# Jafar_-_EasyEDA_-_Schematic_Export.net
KiCad netlist of a schematic drawn in EasyEDA
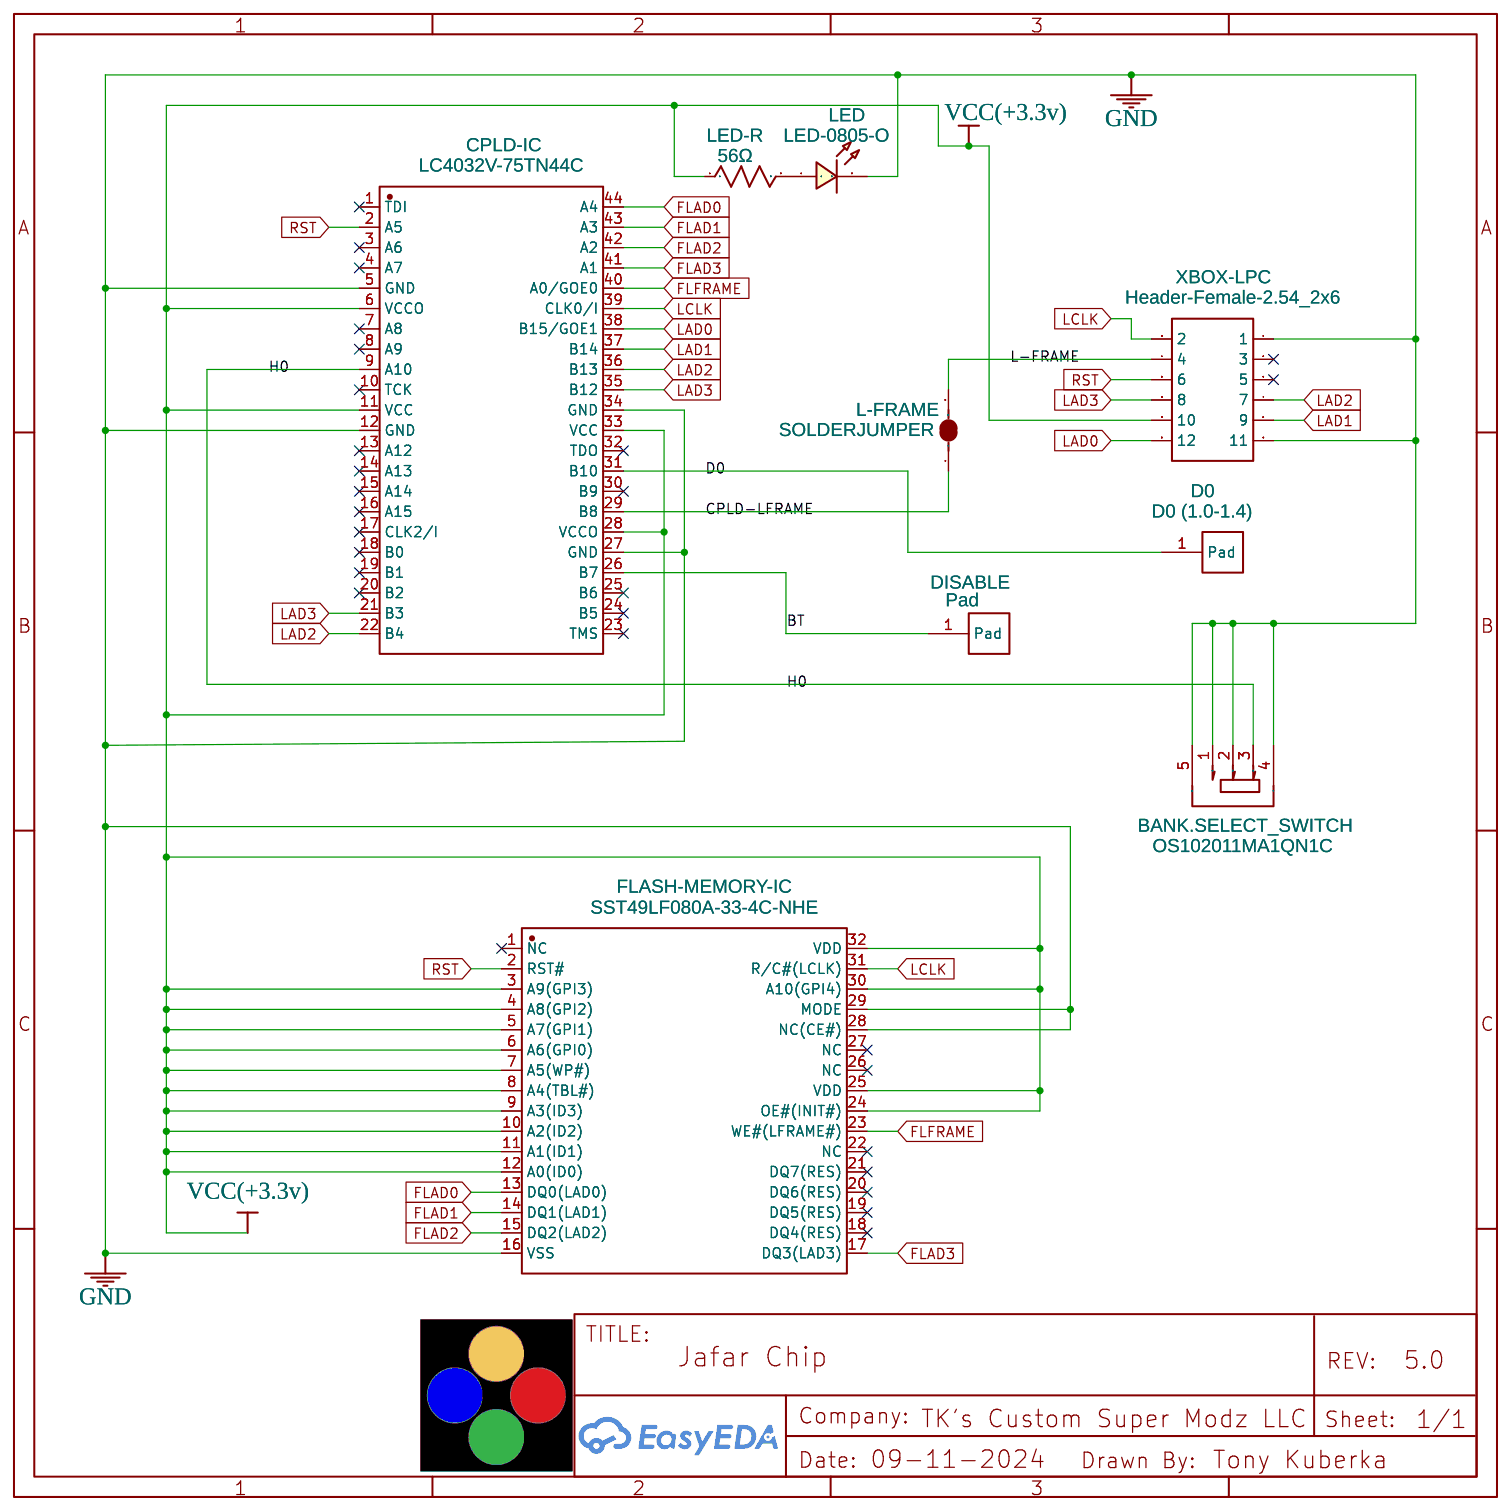
[diagram p0: schematic sheet]

(export (version "E")
  (design (tool "Eeschema 10.0.6"))
  (components
    (comp (ref "BANK.SELECT_SWITCH")
      (value "OS102011MA1QN1C")
      (fields (field (name "Manufacturer") "C&K"))
      (libsource (lib "") (part "OS102011MA1QN1C"))
    )
    (comp (ref "CPLD-IC")
      (value "LC4032V-75TN44C")
      (fields (field (name "Manufacturer") "LATTICE(莱迪思)"))
      (libsource (lib "") (part "LC4032V-75TN44C"))
    )
    (comp (ref "D0") (value "D0 (1.0-1.4)") (libsource (lib "") (part "SOLDER PAD_1")))
    (comp (ref "DISABLE") (value "Pad") (libsource (lib "") (part "SOLDER PAD")))
    (comp (ref "FLASH-MEMORY-IC")
      (value "SST49LF080A-33-4C-NHE")
      (fields (field (name "Manufacturer") "MICROCHIP(美国微芯)"))
      (libsource (lib "") (part "SST49LF080A-33-4C-NHE"))
    )
    (comp (ref "L-FRAME") (value "SOLDERJUMPER") (libsource (lib "") (part "SOLDERJUMPER-OLDNC2")))
    (comp (ref "LED")
      (value "LED-0805-O")
      (fields
        (field (name "Manufacturer Part") "SZYY0805O")
        (field (name "Manufacturer") "Yongyu Photoelectric")
      )
      (libsource (lib "") (part "LED-0805-ORANGE"))
    )
    (comp (ref "LED-R") (value "56Ω") (libsource (lib "") (part "R_0805_US")))
    (comp (ref "XBOX-LPC")
      (value "Header-Female-2.54_2x6")
      (fields (field (name "Manufacturer Part") "2.54-2*6P母") (field (name "Manufacturer") "BOOMELE(博穆精密)"))
      (libsource (lib "") (part "Header-Female-2.54_2x6"))
    )
  )
  (nets
    (net (code "1") (name "/BT") (class "Default")
      (node (ref "CPLD-IC") (pin "26") (pinfunction "B7_26") (pintype "unspecified"))
      (node (ref "DISABLE") (pin "1") (pinfunction "Pad_1") (pintype "unspecified"))
    )
    (net (code "2") (name "/CPLD-LFRAME") (class "Default")
      (node (ref "CPLD-IC") (pin "29") (pinfunction "B8_29") (pintype "unspecified"))
      (node (ref "L-FRAME") (pin "1") (pinfunction "1_1") (pintype "unspecified"))
    )
    (net (code "3") (name "/D0") (class "Default")
      (node (ref "CPLD-IC") (pin "31") (pinfunction "B10_31") (pintype "unspecified"))
      (node (ref "D0") (pin "1") (pinfunction "Pad_1") (pintype "unspecified"))
    )
    (net (code "4") (name "/H0") (class "Default")
      (node (ref "BANK.SELECT_SWITCH") (pin "3") (pinfunction "3_3") (pintype "unspecified"))
      (node (ref "CPLD-IC") (pin "9") (pinfunction "A10_9") (pintype "unspecified"))
    )
    (net (code "5") (name "/L-FRAME") (class "Default")
      (node (ref "L-FRAME") (pin "2") (pinfunction "2_2") (pintype "unspecified"))
      (node (ref "XBOX-LPC") (pin "4") (pinfunction "4_4") (pintype "input"))
    )
    (net (code "6") (name "FLAD0") (class "Default")
      (node (ref "CPLD-IC") (pin "44") (pinfunction "A4_44") (pintype "unspecified"))
      (node (ref "FLASH-MEMORY-IC") (pin "13") (pinfunction "DQ0(LAD0)_13") (pintype "unspecified"))
    )
    (net (code "7") (name "FLAD1") (class "Default")
      (node (ref "CPLD-IC") (pin "43") (pinfunction "A3_43") (pintype "unspecified"))
      (node (ref "FLASH-MEMORY-IC") (pin "14") (pinfunction "DQ1(LAD1)_14") (pintype "unspecified"))
    )
    (net (code "8") (name "FLAD2") (class "Default")
      (node (ref "CPLD-IC") (pin "42") (pinfunction "A2_42") (pintype "unspecified"))
      (node (ref "FLASH-MEMORY-IC") (pin "15") (pinfunction "DQ2(LAD2)_15") (pintype "unspecified"))
    )
    (net (code "9") (name "FLAD3") (class "Default")
      (node (ref "CPLD-IC") (pin "41") (pinfunction "A1_41") (pintype "unspecified"))
      (node (ref "FLASH-MEMORY-IC") (pin "17") (pinfunction "DQ3(LAD3)_17") (pintype "unspecified"))
    )
    (net (code "10") (name "FLFRAME") (class "Default")
      (node (ref "CPLD-IC") (pin "40") (pinfunction "A0/GOE0_40") (pintype "unspecified"))
      (node (ref "FLASH-MEMORY-IC") (pin "23") (pinfunction "WE#(LFRAME#)_23") (pintype "unspecified"))
    )
    (net (code "11") (name "GND") (class "Default")
      (node (ref "BANK.SELECT_SWITCH") (pin "1") (pinfunction "1_1") (pintype "unspecified"))
      (node (ref "BANK.SELECT_SWITCH") (pin "2") (pinfunction "2_2") (pintype "unspecified"))
      (node (ref "BANK.SELECT_SWITCH") (pin "4") (pinfunction "4_4") (pintype "unspecified"))
      (node (ref "BANK.SELECT_SWITCH") (pin "5") (pinfunction "5_5") (pintype "unspecified"))
      (node (ref "CPLD-IC") (pin "12") (pinfunction "GND_12") (pintype "unspecified"))
      (node (ref "CPLD-IC") (pin "27") (pinfunction "GND_27") (pintype "unspecified"))
      (node (ref "CPLD-IC") (pin "34") (pinfunction "GND_34") (pintype "unspecified"))
      (node (ref "CPLD-IC") (pin "5") (pinfunction "GND_5") (pintype "unspecified"))
      (node (ref "FLASH-MEMORY-IC") (pin "16") (pinfunction "VSS_16") (pintype "unspecified"))
      (node (ref "FLASH-MEMORY-IC") (pin "28") (pinfunction "NC(CE#)_28") (pintype "unspecified"))
      (node (ref "FLASH-MEMORY-IC") (pin "29") (pinfunction "MODE_29") (pintype "unspecified"))
      (node (ref "LED") (pin "2") (pinfunction "2_2") (pintype "unspecified"))
      (node (ref "XBOX-LPC") (pin "1") (pinfunction "1_1") (pintype "input"))
      (node (ref "XBOX-LPC") (pin "11") (pinfunction "11_11") (pintype "input"))
    )
    (net (code "12") (name "LAD0") (class "Default")
      (node (ref "CPLD-IC") (pin "38") (pinfunction "B15/GOE1_38") (pintype "unspecified"))
      (node (ref "XBOX-LPC") (pin "12") (pinfunction "12_12") (pintype "input"))
    )
    (net (code "13") (name "LAD1") (class "Default")
      (node (ref "CPLD-IC") (pin "37") (pinfunction "B14_37") (pintype "unspecified"))
      (node (ref "XBOX-LPC") (pin "9") (pinfunction "9_9") (pintype "input"))
    )
    (net (code "14") (name "LAD2") (class "Default")
      (node (ref "CPLD-IC") (pin "22") (pinfunction "B4_22") (pintype "unspecified"))
      (node (ref "CPLD-IC") (pin "36") (pinfunction "B13_36") (pintype "unspecified"))
      (node (ref "XBOX-LPC") (pin "7") (pinfunction "7_7") (pintype "input"))
    )
    (net (code "15") (name "LAD3") (class "Default")
      (node (ref "CPLD-IC") (pin "21") (pinfunction "B3_21") (pintype "unspecified"))
      (node (ref "CPLD-IC") (pin "35") (pinfunction "B12_35") (pintype "unspecified"))
      (node (ref "XBOX-LPC") (pin "8") (pinfunction "8_8") (pintype "input"))
    )
    (net (code "16") (name "LCLK") (class "Default")
      (node (ref "CPLD-IC") (pin "39") (pinfunction "CLK0/I_39") (pintype "unspecified"))
      (node (ref "FLASH-MEMORY-IC") (pin "31") (pinfunction "R/C#(LCLK)_31") (pintype "unspecified"))
      (node (ref "XBOX-LPC") (pin "2") (pinfunction "2_2") (pintype "input"))
    )
    (net (code "17") (name "Net-(LED-Pad1)") (class "Default")
      (node (ref "LED") (pin "1") (pinfunction "1_1") (pintype "unspecified"))
      (node (ref "LED-R") (pin "2") (pinfunction "2_2") (pintype "unspecified"))
    )
    (net (code "18") (name "RST") (class "Default")
      (node (ref "CPLD-IC") (pin "2") (pinfunction "A5_2") (pintype "unspecified"))
      (node (ref "FLASH-MEMORY-IC") (pin "2") (pinfunction "RST#_2") (pintype "unspecified"))
      (node (ref "XBOX-LPC") (pin "6") (pinfunction "6_6") (pintype "input"))
    )
    (net (code "19") (name "VCC(+3.3v)") (class "Default")
      (node (ref "CPLD-IC") (pin "11") (pinfunction "VCC_11") (pintype "unspecified"))
      (node (ref "CPLD-IC") (pin "28") (pinfunction "VCCO_28") (pintype "unspecified"))
      (node (ref "CPLD-IC") (pin "33") (pinfunction "VCC_33") (pintype "unspecified"))
      (node (ref "CPLD-IC") (pin "6") (pinfunction "VCCO_6") (pintype "unspecified"))
      (node (ref "FLASH-MEMORY-IC") (pin "10") (pinfunction "A2(ID2)_10") (pintype "unspecified"))
      (node (ref "FLASH-MEMORY-IC") (pin "11") (pinfunction "A1(ID1)_11") (pintype "unspecified"))
      (node (ref "FLASH-MEMORY-IC") (pin "12") (pinfunction "A0(ID0)_12") (pintype "unspecified"))
      (node (ref "FLASH-MEMORY-IC") (pin "24") (pinfunction "OE#(INIT#)_24") (pintype "unspecified"))
      (node (ref "FLASH-MEMORY-IC") (pin "25") (pinfunction "VDD_25") (pintype "unspecified"))
      (node (ref "FLASH-MEMORY-IC") (pin "3") (pinfunction "A9(GPI3)_3") (pintype "unspecified"))
      (node (ref "FLASH-MEMORY-IC") (pin "30") (pinfunction "A10(GPI4)_30") (pintype "unspecified"))
      (node (ref "FLASH-MEMORY-IC") (pin "32") (pinfunction "VDD_32") (pintype "unspecified"))
      (node (ref "FLASH-MEMORY-IC") (pin "4") (pinfunction "A8(GPI2)_4") (pintype "unspecified"))
      (node (ref "FLASH-MEMORY-IC") (pin "5") (pinfunction "A7(GPI1)_5") (pintype "unspecified"))
      (node (ref "FLASH-MEMORY-IC") (pin "6") (pinfunction "A6(GPI0)_6") (pintype "unspecified"))
      (node (ref "FLASH-MEMORY-IC") (pin "7") (pinfunction "A5(WP#)_7") (pintype "unspecified"))
      (node (ref "FLASH-MEMORY-IC") (pin "8") (pinfunction "A4(TBL#)_8") (pintype "unspecified"))
      (node (ref "FLASH-MEMORY-IC") (pin "9") (pinfunction "A3(ID3)_9") (pintype "unspecified"))
      (node (ref "LED-R") (pin "1") (pinfunction "1_1") (pintype "unspecified"))
      (node (ref "XBOX-LPC") (pin "10") (pinfunction "10_10") (pintype "input"))
    )
    (net (code "20") (name "unconnected-(CPLD-IC-A6-Pad3)") (class "Default")
      (node (ref "CPLD-IC") (pin "3") (pinfunction "A6_3") (pintype "unspecified+no_connect"))
    )
    (net (code "21") (name "unconnected-(CPLD-IC-A7-Pad4)") (class "Default")
      (node (ref "CPLD-IC") (pin "4") (pinfunction "A7_4") (pintype "unspecified+no_connect"))
    )
    (net (code "22") (name "unconnected-(CPLD-IC-A8-Pad7)") (class "Default")
      (node (ref "CPLD-IC") (pin "7") (pinfunction "A8_7") (pintype "unspecified+no_connect"))
    )
    (net (code "23") (name "unconnected-(CPLD-IC-A9-Pad8)") (class "Default")
      (node (ref "CPLD-IC") (pin "8") (pinfunction "A9_8") (pintype "unspecified+no_connect"))
    )
    (net (code "24") (name "unconnected-(CPLD-IC-A12-Pad13)") (class "Default")
      (node (ref "CPLD-IC") (pin "13") (pinfunction "A12_13") (pintype "unspecified+no_connect"))
    )
    (net (code "25") (name "unconnected-(CPLD-IC-A13-Pad14)") (class "Default")
      (node (ref "CPLD-IC") (pin "14") (pinfunction "A13_14") (pintype "unspecified+no_connect"))
    )
    (net (code "26") (name "unconnected-(CPLD-IC-A14-Pad15)") (class "Default")
      (node (ref "CPLD-IC") (pin "15") (pinfunction "A14_15") (pintype "unspecified+no_connect"))
    )
    (net (code "27") (name "unconnected-(CPLD-IC-A15-Pad16)") (class "Default")
      (node (ref "CPLD-IC") (pin "16") (pinfunction "A15_16") (pintype "unspecified+no_connect"))
    )
    (net (code "28") (name "unconnected-(CPLD-IC-B0-Pad18)") (class "Default")
      (node (ref "CPLD-IC") (pin "18") (pinfunction "B0_18") (pintype "unspecified+no_connect"))
    )
    (net (code "29") (name "unconnected-(CPLD-IC-B1-Pad19)") (class "Default")
      (node (ref "CPLD-IC") (pin "19") (pinfunction "B1_19") (pintype "unspecified+no_connect"))
    )
    (net (code "30") (name "unconnected-(CPLD-IC-B2-Pad20)") (class "Default")
      (node (ref "CPLD-IC") (pin "20") (pinfunction "B2_20") (pintype "unspecified+no_connect"))
    )
    (net (code "31") (name "unconnected-(CPLD-IC-B5-Pad24)") (class "Default")
      (node (ref "CPLD-IC") (pin "24") (pinfunction "B5_24") (pintype "unspecified+no_connect"))
    )
    (net (code "32") (name "unconnected-(CPLD-IC-B6-Pad25)") (class "Default")
      (node (ref "CPLD-IC") (pin "25") (pinfunction "B6_25") (pintype "unspecified+no_connect"))
    )
    (net (code "33") (name "unconnected-(CPLD-IC-B9-Pad30)") (class "Default")
      (node (ref "CPLD-IC") (pin "30") (pinfunction "B9_30") (pintype "unspecified+no_connect"))
    )
    (net (code "34") (name "unconnected-(CPLD-IC-CLK2{slash}I-Pad17)") (class "Default")
      (node (ref "CPLD-IC") (pin "17") (pinfunction "CLK2/I_17") (pintype "unspecified+no_connect"))
    )
    (net (code "35") (name "unconnected-(CPLD-IC-TCK-Pad10)") (class "Default")
      (node (ref "CPLD-IC") (pin "10") (pinfunction "TCK_10") (pintype "unspecified+no_connect"))
    )
    (net (code "36") (name "unconnected-(CPLD-IC-TDI-Pad1)") (class "Default")
      (node (ref "CPLD-IC") (pin "1") (pinfunction "TDI_1") (pintype "unspecified+no_connect"))
    )
    (net (code "37") (name "unconnected-(CPLD-IC-TDO-Pad32)") (class "Default")
      (node (ref "CPLD-IC") (pin "32") (pinfunction "TDO_32") (pintype "unspecified+no_connect"))
    )
    (net (code "38") (name "unconnected-(CPLD-IC-TMS-Pad23)") (class "Default")
      (node (ref "CPLD-IC") (pin "23") (pinfunction "TMS_23") (pintype "unspecified+no_connect"))
    )
    (net (code "39") (name "unconnected-(FLASH-MEMORY-IC-DQ4(RES)-Pad18)") (class "Default")
      (node (ref "FLASH-MEMORY-IC") (pin "18") (pinfunction "DQ4(RES)_18") (pintype "unspecified+no_connect"))
    )
    (net (code "40") (name "unconnected-(FLASH-MEMORY-IC-DQ5(RES)-Pad19)") (class "Default")
      (node (ref "FLASH-MEMORY-IC") (pin "19") (pinfunction "DQ5(RES)_19") (pintype "unspecified+no_connect"))
    )
    (net (code "41") (name "unconnected-(FLASH-MEMORY-IC-DQ6(RES)-Pad20)") (class "Default")
      (node (ref "FLASH-MEMORY-IC") (pin "20") (pinfunction "DQ6(RES)_20") (pintype "unspecified+no_connect"))
    )
    (net (code "42") (name "unconnected-(FLASH-MEMORY-IC-DQ7(RES)-Pad21)") (class "Default")
      (node (ref "FLASH-MEMORY-IC") (pin "21") (pinfunction "DQ7(RES)_21") (pintype "unspecified+no_connect"))
    )
    (net (code "43") (name "unconnected-(FLASH-MEMORY-IC-NC-Pad1)") (class "Default")
      (node (ref "FLASH-MEMORY-IC") (pin "1") (pinfunction "NC_1") (pintype "unspecified+no_connect"))
    )
    (net (code "44") (name "unconnected-(FLASH-MEMORY-IC-NC-Pad22)") (class "Default")
      (node (ref "FLASH-MEMORY-IC") (pin "22") (pinfunction "NC_22") (pintype "unspecified+no_connect"))
    )
    (net (code "45") (name "unconnected-(FLASH-MEMORY-IC-NC-Pad26)") (class "Default")
      (node (ref "FLASH-MEMORY-IC") (pin "26") (pinfunction "NC_26") (pintype "unspecified+no_connect"))
    )
    (net (code "46") (name "unconnected-(FLASH-MEMORY-IC-NC-Pad27)") (class "Default")
      (node (ref "FLASH-MEMORY-IC") (pin "27") (pinfunction "NC_27") (pintype "unspecified+no_connect"))
    )
    (net (code "47") (name "unconnected-(XBOX-LPC-Pad3)") (class "Default")
      (node (ref "XBOX-LPC") (pin "3") (pinfunction "3_3") (pintype "input+no_connect"))
    )
    (net (code "48") (name "unconnected-(XBOX-LPC-Pad5)") (class "Default")
      (node (ref "XBOX-LPC") (pin "5") (pinfunction "5_5") (pintype "input+no_connect"))
    )
  )
)
